# amp_tda8425_v_1_0.net
KiCad netlist of a schematic drawn in EAGLE
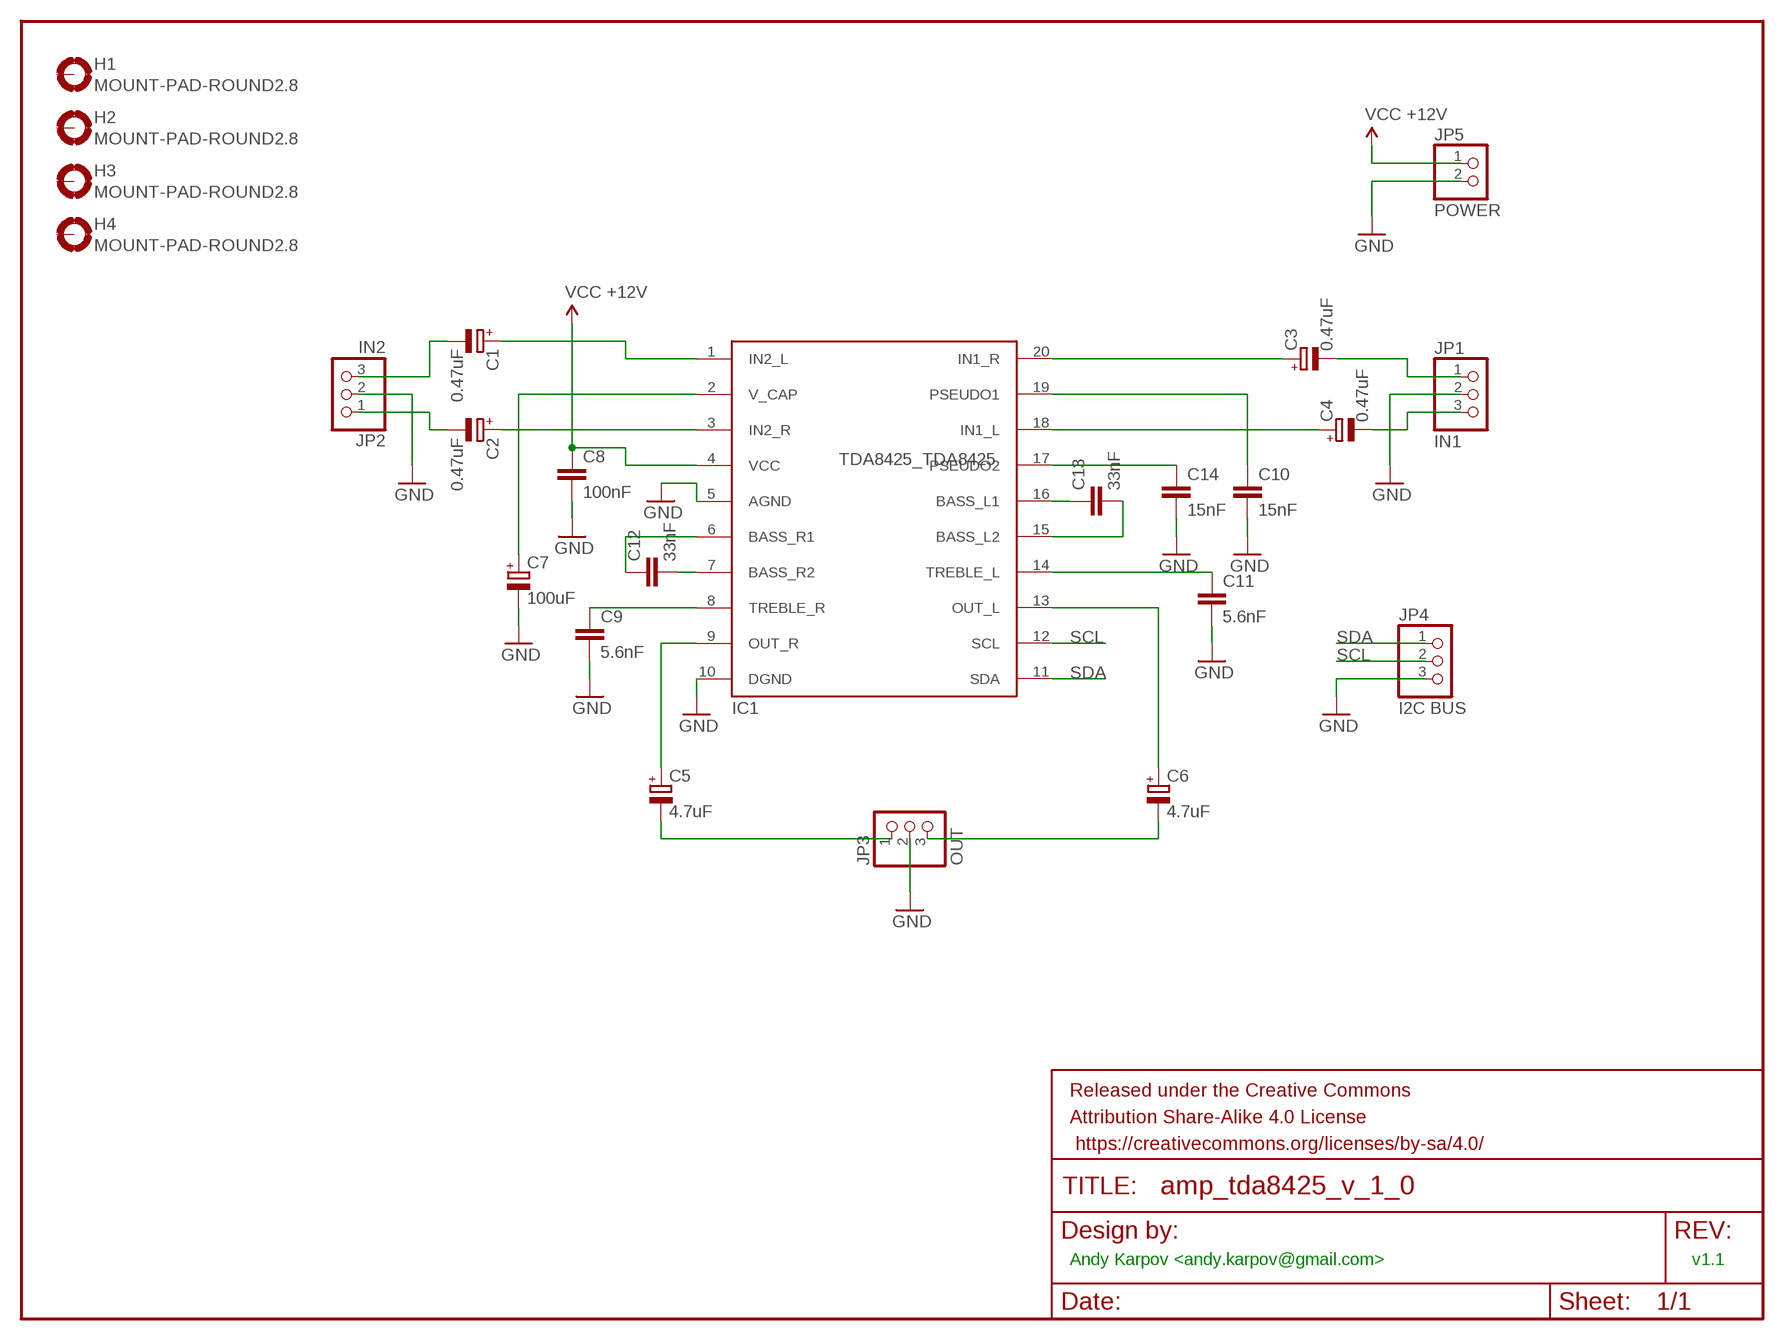
[diagram p0: schematic, sheet 1]

(export (version "E")
  (design (tool "Eeschema 10.0.6"))
  (components
    (comp (ref "C1")
      (value "0.47uF")
      (footprint "eagle-import:E2,5-6")
      (libsource (lib "eagle-import") (part "CPOL-EUE2.5-6"))
    )
    (comp (ref "C2")
      (value "0.47uF")
      (footprint "eagle-import:E2,5-6")
      (libsource (lib "eagle-import") (part "CPOL-EUE2.5-6"))
    )
    (comp (ref "C3")
      (value "0.47uF")
      (footprint "eagle-import:E2,5-6")
      (libsource (lib "eagle-import") (part "CPOL-EUE2.5-6"))
    )
    (comp (ref "C4")
      (value "0.47uF")
      (footprint "eagle-import:E2,5-6")
      (libsource (lib "eagle-import") (part "CPOL-EUE2.5-6"))
    )
    (comp (ref "C5")
      (value "4.7uF")
      (footprint "eagle-import:E2,5-6")
      (libsource (lib "eagle-import") (part "CPOL-EUE2.5-6"))
    )
    (comp (ref "C6")
      (value "4.7uF")
      (footprint "eagle-import:E2,5-6")
      (libsource (lib "eagle-import") (part "CPOL-EUE2.5-6"))
    )
    (comp (ref "C7")
      (value "100uF")
      (footprint "eagle-import:E2,5-6")
      (libsource (lib "eagle-import") (part "CPOL-EUE2.5-6"))
    )
    (comp (ref "C8")
      (value "100nF")
      (footprint "eagle-import:C025-025X050")
      (libsource (lib "eagle-import") (part "C-EU025-025X050"))
    )
    (comp (ref "C9")
      (value "5.6nF")
      (footprint "eagle-import:C025-025X050")
      (libsource (lib "eagle-import") (part "C-EU025-025X050"))
    )
    (comp (ref "C10")
      (value "15nF")
      (footprint "eagle-import:C025-025X050")
      (libsource (lib "eagle-import") (part "C-EU025-025X050"))
    )
    (comp (ref "C11")
      (value "5.6nF")
      (footprint "eagle-import:C025-025X050")
      (libsource (lib "eagle-import") (part "C-EU025-025X050"))
    )
    (comp (ref "C12")
      (value "33nF")
      (footprint "eagle-import:C025-025X050")
      (libsource (lib "eagle-import") (part "C-EU025-025X050"))
    )
    (comp (ref "C13")
      (value "33nF")
      (footprint "eagle-import:C025-025X050")
      (libsource (lib "eagle-import") (part "C-EU025-025X050"))
    )
    (comp (ref "C14")
      (value "15nF")
      (footprint "eagle-import:C025-025X050")
      (libsource (lib "eagle-import") (part "C-EU025-025X050"))
    )
    (comp (ref "FRAME1")
      (value "FRAME-LETTER")
      (footprint "eagle-import:CREATIVE_COMMONS")
      (libsource (lib "eagle-import") (part "FRAME-LETTER"))
    )
    (comp (ref "H1")
      (value "MOUNT-PAD-ROUND2.8")
      (footprint "eagle-import:2,8-PAD")
      (libsource (lib "eagle-import") (part "MOUNT-PAD-ROUND2.8"))
    )
    (comp (ref "H2")
      (value "MOUNT-PAD-ROUND2.8")
      (footprint "eagle-import:2,8-PAD")
      (libsource (lib "eagle-import") (part "MOUNT-PAD-ROUND2.8"))
    )
    (comp (ref "H3")
      (value "MOUNT-PAD-ROUND2.8")
      (footprint "eagle-import:2,8-PAD")
      (libsource (lib "eagle-import") (part "MOUNT-PAD-ROUND2.8"))
    )
    (comp (ref "H4")
      (value "MOUNT-PAD-ROUND2.8")
      (footprint "eagle-import:2,8-PAD")
      (libsource (lib "eagle-import") (part "MOUNT-PAD-ROUND2.8"))
    )
    (comp (ref "IC1")
      (value "TDA8425_TDA8425")
      (footprint "eagle-import:TDA8425_DIL20")
      (libsource (lib "eagle-import") (part "TDA8425_TDA8425"))
    )
    (comp (ref "JP1")
      (value "IN1")
      (footprint "eagle-import:1X03")
      (libsource (lib "eagle-import") (part "PINHD-1X3"))
    )
    (comp (ref "JP2")
      (value "IN2")
      (footprint "eagle-import:1X03")
      (libsource (lib "eagle-import") (part "PINHD-1X3"))
    )
    (comp (ref "JP3")
      (value "OUT")
      (footprint "eagle-import:1X03")
      (libsource (lib "eagle-import") (part "PINHD-1X3"))
    )
    (comp (ref "JP4")
      (value "I2C BUS")
      (footprint "eagle-import:1X03")
      (libsource (lib "eagle-import") (part "PINHD-1X3"))
    )
    (comp (ref "JP5")
      (value "POWER")
      (footprint "eagle-import:1X02")
      (libsource (lib "eagle-import") (part "PINHD-1X2"))
    )
  )
  (nets
    (net (code "1") (name "/SCL") (class "Default")
      (node (ref "IC1") (pin "12") (pinfunction "SCL_12") (pintype "bidirectional"))
      (node (ref "JP4") (pin "2") (pinfunction "2_2") (pintype "passive"))
    )
    (net (code "2") (name "/SDA") (class "Default")
      (node (ref "IC1") (pin "11") (pinfunction "SDA_11") (pintype "bidirectional"))
      (node (ref "JP4") (pin "1") (pinfunction "1_1") (pintype "passive"))
    )
    (net (code "3") (name "GND") (class "Default")
      (node (ref "C10") (pin "2") (pinfunction "2_2") (pintype "passive"))
      (node (ref "C11") (pin "2") (pinfunction "2_2") (pintype "passive"))
      (node (ref "C14") (pin "2") (pinfunction "2_2") (pintype "passive"))
      (node (ref "C7") (pin "-") (pinfunction "-_-") (pintype "passive"))
      (node (ref "C8") (pin "2") (pinfunction "2_2") (pintype "passive"))
      (node (ref "C9") (pin "2") (pinfunction "2_2") (pintype "passive"))
      (node (ref "IC1") (pin "10") (pinfunction "DGND_10") (pintype "bidirectional"))
      (node (ref "IC1") (pin "5") (pinfunction "AGND_5") (pintype "bidirectional"))
      (node (ref "JP1") (pin "2") (pinfunction "2_2") (pintype "passive"))
      (node (ref "JP2") (pin "2") (pinfunction "2_2") (pintype "passive"))
      (node (ref "JP3") (pin "2") (pinfunction "2_2") (pintype "passive"))
      (node (ref "JP4") (pin "3") (pinfunction "3_3") (pintype "passive"))
      (node (ref "JP5") (pin "2") (pinfunction "2_2") (pintype "passive"))
    )
    (net (code "4") (name "Net-(C1-Pad-)") (class "Default")
      (node (ref "C1") (pin "-") (pinfunction "-_-") (pintype "passive"))
      (node (ref "JP2") (pin "3") (pinfunction "3_3") (pintype "passive"))
    )
    (net (code "5") (name "Net-(C2-Pad-)") (class "Default")
      (node (ref "C2") (pin "-") (pinfunction "-_-") (pintype "passive"))
      (node (ref "JP2") (pin "1") (pinfunction "1_1") (pintype "passive"))
    )
    (net (code "6") (name "Net-(C3-Pad-)") (class "Default")
      (node (ref "C3") (pin "-") (pinfunction "-_-") (pintype "passive"))
      (node (ref "JP1") (pin "1") (pinfunction "1_1") (pintype "passive"))
    )
    (net (code "7") (name "Net-(C4-Pad-)") (class "Default")
      (node (ref "C4") (pin "-") (pinfunction "-_-") (pintype "passive"))
      (node (ref "JP1") (pin "3") (pinfunction "3_3") (pintype "passive"))
    )
    (net (code "8") (name "Net-(C5-Pad-)") (class "Default")
      (node (ref "C5") (pin "-") (pinfunction "-_-") (pintype "passive"))
      (node (ref "JP3") (pin "1") (pinfunction "1_1") (pintype "passive"))
    )
    (net (code "9") (name "Net-(C6-Pad-)") (class "Default")
      (node (ref "C6") (pin "-") (pinfunction "-_-") (pintype "passive"))
      (node (ref "JP3") (pin "3") (pinfunction "3_3") (pintype "passive"))
    )
    (net (code "10") (name "Net-(IC1-BASS_L1)") (class "Default")
      (node (ref "C13") (pin "1") (pinfunction "1_1") (pintype "passive"))
      (node (ref "IC1") (pin "16") (pinfunction "BASS_L1_16") (pintype "bidirectional"))
    )
    (net (code "11") (name "Net-(IC1-BASS_L2)") (class "Default")
      (node (ref "C13") (pin "2") (pinfunction "2_2") (pintype "passive"))
      (node (ref "IC1") (pin "15") (pinfunction "BASS_L2_15") (pintype "bidirectional"))
    )
    (net (code "12") (name "Net-(IC1-BASS_R1)") (class "Default")
      (node (ref "C12") (pin "1") (pinfunction "1_1") (pintype "passive"))
      (node (ref "IC1") (pin "6") (pinfunction "BASS_R1_6") (pintype "bidirectional"))
    )
    (net (code "13") (name "Net-(IC1-BASS_R2)") (class "Default")
      (node (ref "C12") (pin "2") (pinfunction "2_2") (pintype "passive"))
      (node (ref "IC1") (pin "7") (pinfunction "BASS_R2_7") (pintype "bidirectional"))
    )
    (net (code "14") (name "Net-(IC1-IN1_L)") (class "Default")
      (node (ref "C4") (pin "+") (pinfunction "+_+") (pintype "passive"))
      (node (ref "IC1") (pin "18") (pinfunction "IN1_L_18") (pintype "bidirectional"))
    )
    (net (code "15") (name "Net-(IC1-IN1_R)") (class "Default")
      (node (ref "C3") (pin "+") (pinfunction "+_+") (pintype "passive"))
      (node (ref "IC1") (pin "20") (pinfunction "IN1_R_20") (pintype "bidirectional"))
    )
    (net (code "16") (name "Net-(IC1-IN2_L)") (class "Default")
      (node (ref "C1") (pin "+") (pinfunction "+_+") (pintype "passive"))
      (node (ref "IC1") (pin "1") (pinfunction "IN2_L_1") (pintype "bidirectional"))
    )
    (net (code "17") (name "Net-(IC1-IN2_R)") (class "Default")
      (node (ref "C2") (pin "+") (pinfunction "+_+") (pintype "passive"))
      (node (ref "IC1") (pin "3") (pinfunction "IN2_R_3") (pintype "bidirectional"))
    )
    (net (code "18") (name "Net-(IC1-OUT_L)") (class "Default")
      (node (ref "C6") (pin "+") (pinfunction "+_+") (pintype "passive"))
      (node (ref "IC1") (pin "13") (pinfunction "OUT_L_13") (pintype "bidirectional"))
    )
    (net (code "19") (name "Net-(IC1-OUT_R)") (class "Default")
      (node (ref "C5") (pin "+") (pinfunction "+_+") (pintype "passive"))
      (node (ref "IC1") (pin "9") (pinfunction "OUT_R_9") (pintype "bidirectional"))
    )
    (net (code "20") (name "Net-(IC1-PSEUDO1)") (class "Default")
      (node (ref "C10") (pin "1") (pinfunction "1_1") (pintype "passive"))
      (node (ref "IC1") (pin "19") (pinfunction "PSEUDO1_19") (pintype "bidirectional"))
    )
    (net (code "21") (name "Net-(IC1-PSEUDO2)") (class "Default")
      (node (ref "C14") (pin "1") (pinfunction "1_1") (pintype "passive"))
      (node (ref "IC1") (pin "17") (pinfunction "PSEUDO2_17") (pintype "bidirectional"))
    )
    (net (code "22") (name "Net-(IC1-TREBLE_L)") (class "Default")
      (node (ref "C11") (pin "1") (pinfunction "1_1") (pintype "passive"))
      (node (ref "IC1") (pin "14") (pinfunction "TREBLE_L_14") (pintype "bidirectional"))
    )
    (net (code "23") (name "Net-(IC1-TREBLE_R)") (class "Default")
      (node (ref "C9") (pin "1") (pinfunction "1_1") (pintype "passive"))
      (node (ref "IC1") (pin "8") (pinfunction "TREBLE_R_8") (pintype "bidirectional"))
    )
    (net (code "24") (name "Net-(IC1-V_CAP)") (class "Default")
      (node (ref "C7") (pin "+") (pinfunction "+_+") (pintype "passive"))
      (node (ref "IC1") (pin "2") (pinfunction "V_CAP_2") (pintype "bidirectional"))
    )
    (net (code "25") (name "VCC +12V") (class "Default")
      (node (ref "C8") (pin "1") (pinfunction "1_1") (pintype "passive"))
      (node (ref "IC1") (pin "4") (pinfunction "VCC_4") (pintype "bidirectional"))
      (node (ref "JP5") (pin "1") (pinfunction "1_1") (pintype "passive"))
    )
    (net (code "26") (name "unconnected-(H1-MOUNT-PadB2,8)") (class "Default")
      (node (ref "H1") (pin "B2,8") (pinfunction "MOUNT_B2,8") (pintype "passive"))
    )
    (net (code "27") (name "unconnected-(H2-MOUNT-PadB2,8)") (class "Default")
      (node (ref "H2") (pin "B2,8") (pinfunction "MOUNT_B2,8") (pintype "passive"))
    )
    (net (code "28") (name "unconnected-(H3-MOUNT-PadB2,8)") (class "Default")
      (node (ref "H3") (pin "B2,8") (pinfunction "MOUNT_B2,8") (pintype "passive"))
    )
    (net (code "29") (name "unconnected-(H4-MOUNT-PadB2,8)") (class "Default")
      (node (ref "H4") (pin "B2,8") (pinfunction "MOUNT_B2,8") (pintype "passive"))
    )
  )
)
